# Homodyne_detector.net
KiCad netlist of a schematic drawn in Altium Designer
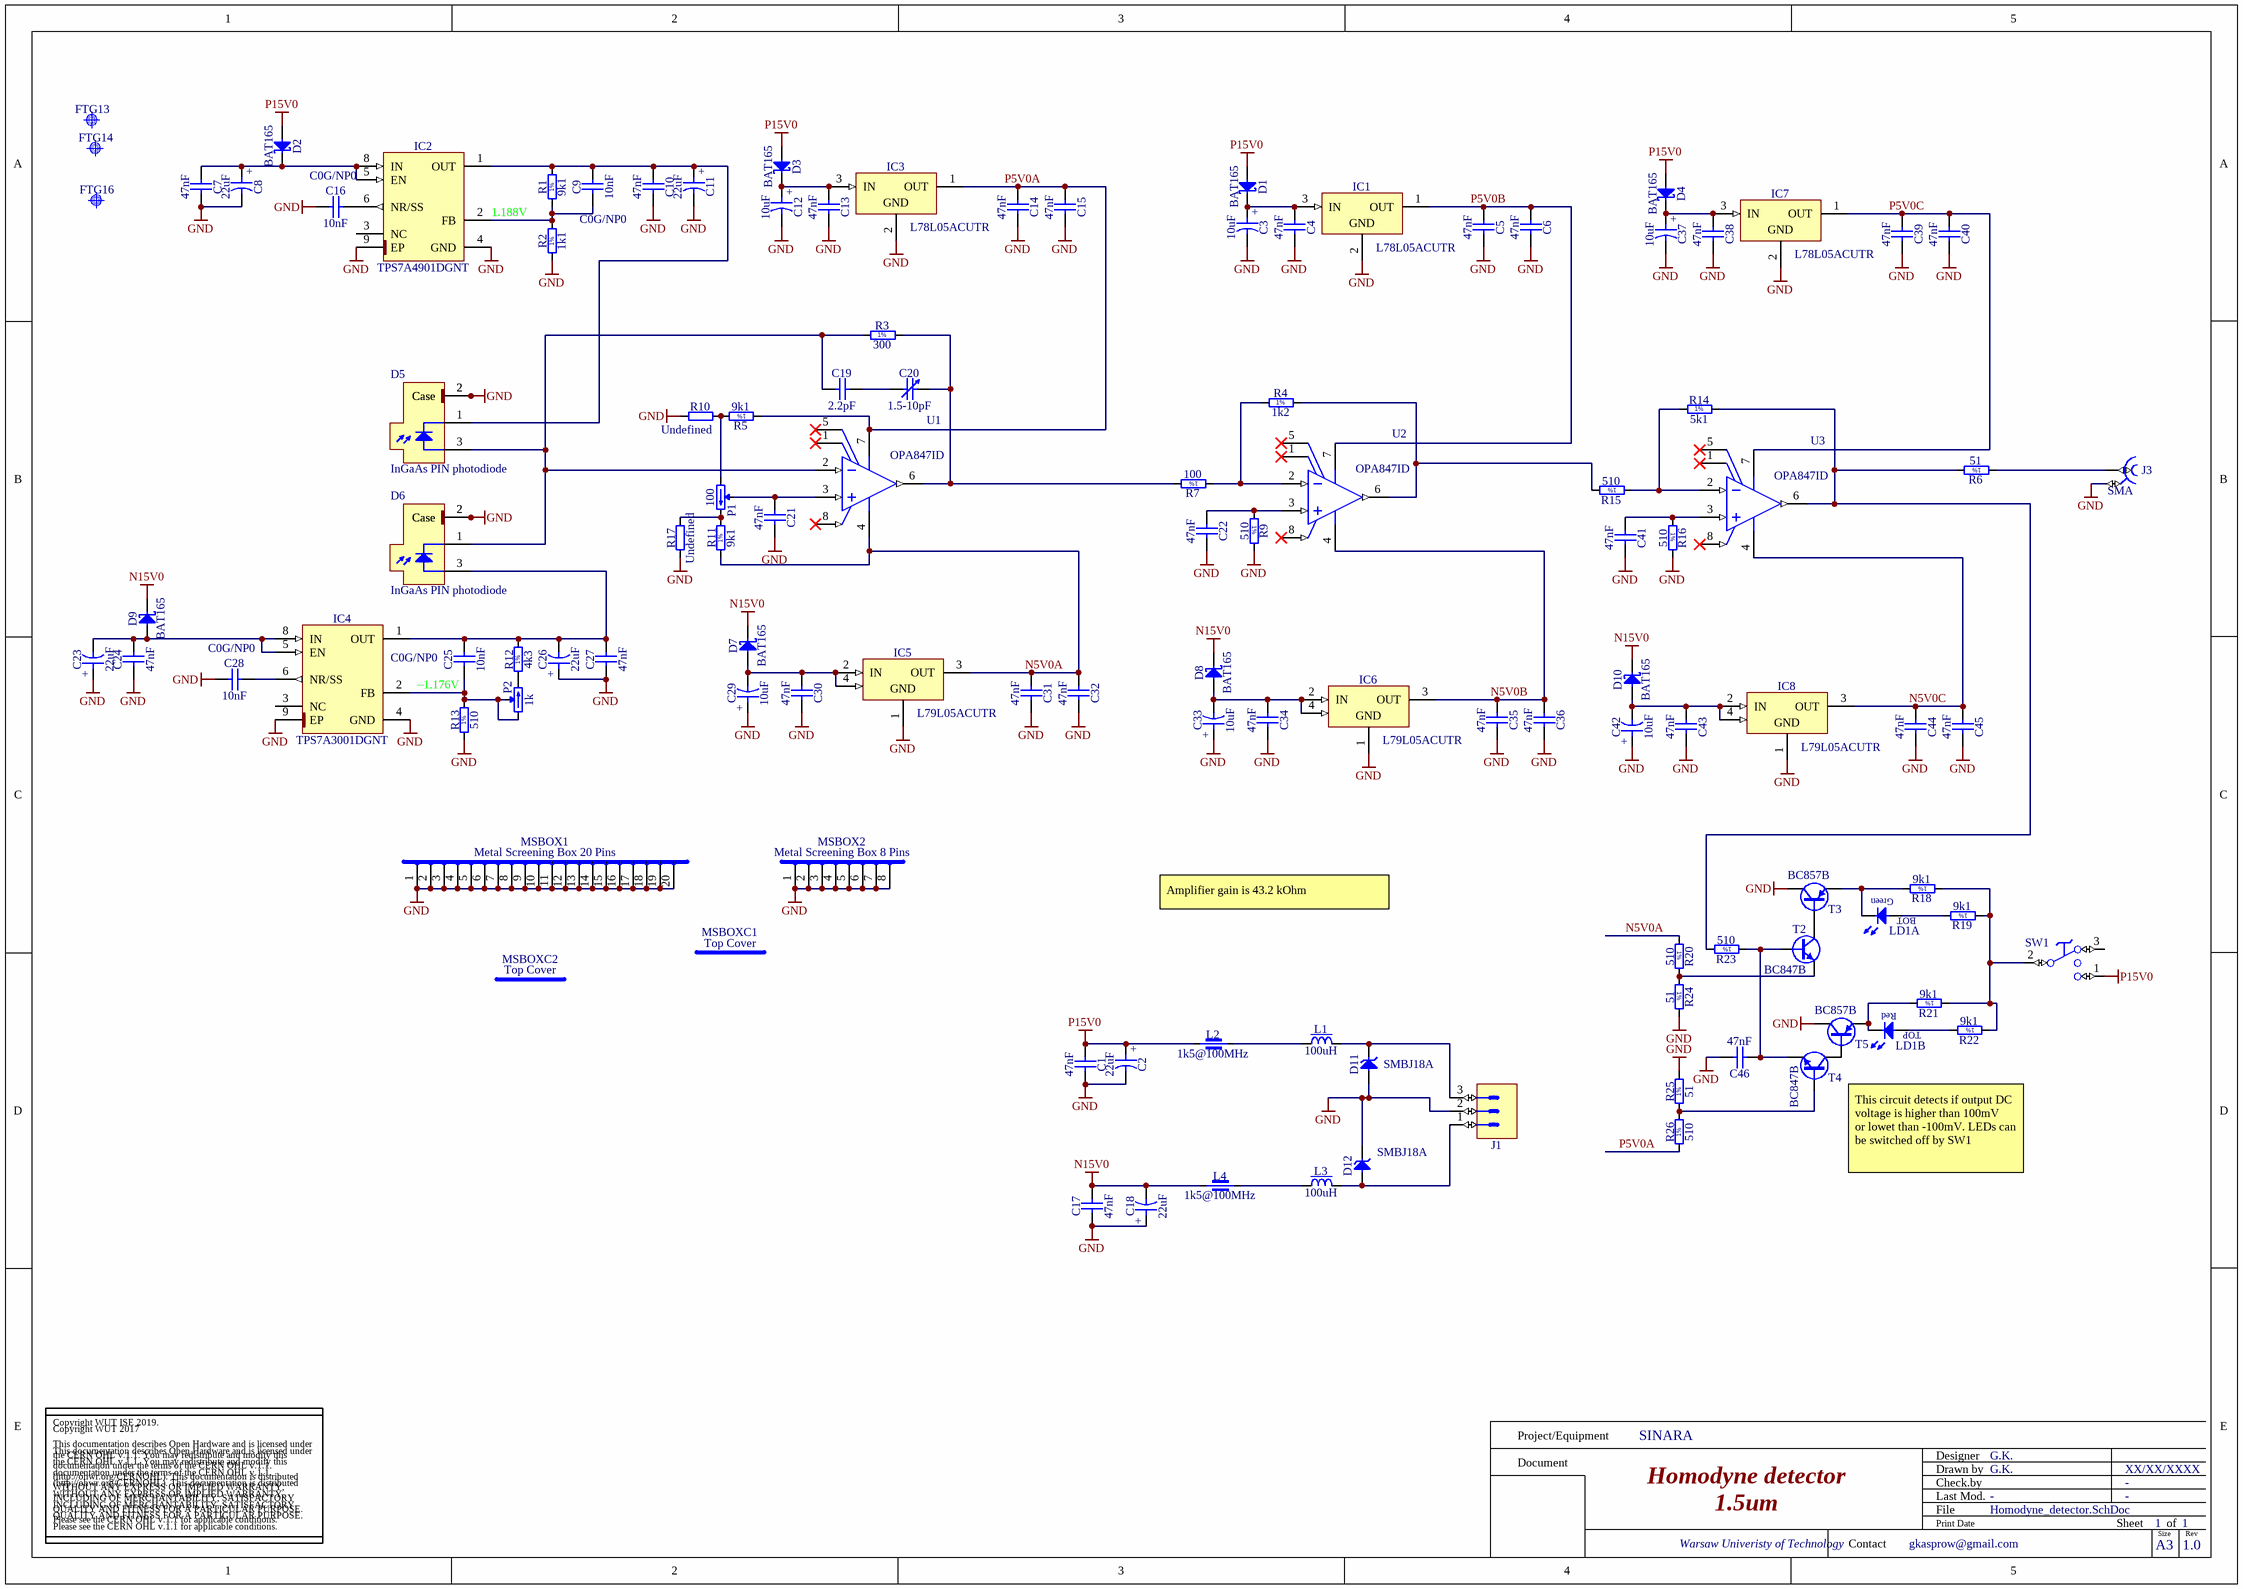
[diagram p0: Homodyne_detector.SchDoc]

(export (version "E")
  (design (tool "Eeschema 10.0.6"))
  (components
    (comp (ref "C1")
      (value "47nF")
      (footprint "CAPC2012X135N")
      (description "Non-polarised capacitor")
      (fields
        (field (name "PART NUMBER") "CC0805_47NF_25V_5%_C0G")
        (field (name "VOLTAGE") "25V")
        (field (name "AUTHOR") "CERN DEM JLC")
      )
      (libsource (lib "Capacitors") (part "Capacitor - non polarized"))
    )
    (comp (ref "C2")
      (value "22uF")
      (footprint "CAPMP7343X190N")
      (description "Polarised capacitor")
      (fields
        (field (name "PART NUMBER") "CTE7343-19_22UF_20V_20%_LESR0045_KEMET_T520")
        (field (name "VOLTAGE") "20V")
        (field (name "AUTHOR") "CERN DEM JLC")
      )
      (libsource (lib "Capacitors") (part "Capacitor - polarized"))
    )
    (comp (ref "C3")
      (value "10uF")
      (footprint "CAPAE430X540N")
      (description "Polarised capacitor")
      (fields
        (field (name "PART NUMBER") "CAE430-540_10UF_25V_20%")
        (field (name "VOLTAGE") "25V")
        (field (name "AUTHOR") "CERN DEM JLC")
      )
      (libsource (lib "Capacitors") (part "Capacitor - polarized"))
    )
    (comp (ref "C4")
      (value "47nF")
      (footprint "CAPC2012X135N")
      (description "Non-polarised capacitor")
      (fields
        (field (name "PART NUMBER") "CC0805_47NF_25V_5%_C0G")
        (field (name "VOLTAGE") "25V")
        (field (name "AUTHOR") "CERN DEM JLC")
      )
      (libsource (lib "Capacitors") (part "Capacitor - non polarized"))
    )
    (comp (ref "C5")
      (value "47nF")
      (footprint "CAPC2012X135N")
      (description "Non-polarised capacitor")
      (fields
        (field (name "PART NUMBER") "CC0805_47NF_25V_5%_C0G")
        (field (name "VOLTAGE") "25V")
        (field (name "AUTHOR") "CERN DEM JLC")
      )
      (libsource (lib "Capacitors") (part "Capacitor - non polarized"))
    )
    (comp (ref "C6")
      (value "47nF")
      (footprint "CAPC2012X135N")
      (description "Non-polarised capacitor")
      (fields
        (field (name "PART NUMBER") "CC0805_47NF_25V_5%_C0G")
        (field (name "VOLTAGE") "25V")
        (field (name "AUTHOR") "CERN DEM JLC")
      )
      (libsource (lib "Capacitors") (part "Capacitor - non polarized"))
    )
    (comp (ref "C7")
      (value "47nF")
      (footprint "CAPC2012X135N")
      (description "Non-polarised capacitor")
      (fields
        (field (name "PART NUMBER") "CC0805_47NF_25V_5%_C0G")
        (field (name "VOLTAGE") "25V")
        (field (name "AUTHOR") "CERN DEM JLC")
      )
      (libsource (lib "Capacitors") (part "Capacitor - non polarized"))
    )
    (comp (ref "C8")
      (value "22uF")
      (footprint "CAPMP7343X190N")
      (description "Polarised capacitor")
      (fields
        (field (name "PART NUMBER") "CTE7343-19_22UF_20V_20%_LESR0045_KEMET_T520")
        (field (name "VOLTAGE") "20V")
        (field (name "AUTHOR") "CERN DEM JLC")
      )
      (libsource (lib "Capacitors") (part "Capacitor - polarized"))
    )
    (comp (ref "C9")
      (value "10nF")
      (footprint "CAPC2012X135N")
      (description "Non-polarised capacitor")
      (fields
        (field (name "PART NUMBER") "CC0805_10NF_50V_5%_C0G")
        (field (name "VOLTAGE") "50V")
        (field (name "TC") "C0G/NP0")
        (field (name "AUTHOR") "CERN DEM JLC")
      )
      (libsource (lib "Capacitors") (part "Capacitor - non polarized"))
    )
    (comp (ref "C10")
      (value "47nF")
      (footprint "CAPC2012X135N")
      (description "Non-polarised capacitor")
      (fields
        (field (name "PART NUMBER") "CC0805_47NF_25V_5%_C0G")
        (field (name "VOLTAGE") "25V")
        (field (name "AUTHOR") "CERN DEM JLC")
      )
      (libsource (lib "Capacitors") (part "Capacitor - non polarized"))
    )
    (comp (ref "C11")
      (value "22uF")
      (footprint "CAPMP7343X190N")
      (description "Polarised capacitor")
      (fields
        (field (name "PART NUMBER") "CTE7343-19_22UF_20V_20%_LESR0045_KEMET_T520")
        (field (name "VOLTAGE") "20V")
        (field (name "AUTHOR") "CERN DEM JLC")
      )
      (libsource (lib "Capacitors") (part "Capacitor - polarized"))
    )
    (comp (ref "C12")
      (value "10uF")
      (footprint "CAPAE430X540N")
      (description "Polarised capacitor")
      (fields
        (field (name "PART NUMBER") "CAE430-540_10UF_25V_20%")
        (field (name "VOLTAGE") "25V")
        (field (name "AUTHOR") "CERN DEM JLC")
      )
      (libsource (lib "Capacitors") (part "Capacitor - polarized"))
    )
    (comp (ref "C13")
      (value "47nF")
      (footprint "CAPC2012X135N")
      (description "Non-polarised capacitor")
      (fields
        (field (name "PART NUMBER") "CC0805_47NF_25V_5%_C0G")
        (field (name "VOLTAGE") "25V")
        (field (name "AUTHOR") "CERN DEM JLC")
      )
      (libsource (lib "Capacitors") (part "Capacitor - non polarized"))
    )
    (comp (ref "C14")
      (value "47nF")
      (footprint "CAPC2012X135N")
      (description "Non-polarised capacitor")
      (fields
        (field (name "PART NUMBER") "CC0805_47NF_25V_5%_C0G")
        (field (name "VOLTAGE") "25V")
        (field (name "AUTHOR") "CERN DEM JLC")
      )
      (libsource (lib "Capacitors") (part "Capacitor - non polarized"))
    )
    (comp (ref "C15")
      (value "47nF")
      (footprint "CAPC2012X135N")
      (description "Non-polarised capacitor")
      (fields
        (field (name "PART NUMBER") "CC0805_47NF_25V_5%_C0G")
        (field (name "VOLTAGE") "25V")
        (field (name "AUTHOR") "CERN DEM JLC")
      )
      (libsource (lib "Capacitors") (part "Capacitor - non polarized"))
    )
    (comp (ref "C16")
      (value "10nF")
      (footprint "CAPC2012X135N")
      (description "Non-polarised capacitor")
      (fields
        (field (name "PART NUMBER") "CC0805_10NF_50V_5%_C0G")
        (field (name "VOLTAGE") "50V")
        (field (name "TC") "C0G/NP0")
        (field (name "AUTHOR") "CERN DEM JLC")
      )
      (libsource (lib "Capacitors") (part "Capacitor - non polarized"))
    )
    (comp (ref "C17")
      (value "47nF")
      (footprint "CAPC2012X135N")
      (description "Non-polarised capacitor")
      (fields
        (field (name "PART NUMBER") "CC0805_47NF_25V_5%_C0G")
        (field (name "VOLTAGE") "25V")
        (field (name "AUTHOR") "CERN DEM JLC")
      )
      (libsource (lib "Capacitors") (part "Capacitor - non polarized"))
    )
    (comp (ref "C18")
      (value "22uF")
      (footprint "CAPMP7343X190N")
      (description "Polarised capacitor")
      (fields
        (field (name "PART NUMBER") "CTE7343-19_22UF_20V_20%_LESR0045_KEMET_T520")
        (field (name "VOLTAGE") "20V")
        (field (name "AUTHOR") "CERN DEM JLC")
      )
      (libsource (lib "Capacitors") (part "Capacitor - polarized"))
    )
    (comp (ref "C19")
      (value "2.2pF")
      (footprint "CAPC1608X87N")
      (description "Non-polarised capacitor")
      (fields
        (field (name "PART NUMBER") "CC0603_2.2PF_50V_0.25PF_NP0")
        (field (name "VOLTAGE") "50V")
        (field (name "AUTHOR") "CERN DEM JLC")
      )
      (libsource (lib "Capacitors") (part "Capacitor - non polarized"))
    )
    (comp (ref "C20")
      (value "1.5-10pF")
      (footprint "CAPV_JOHANSON_9343")
      (description "Adjustable Capacitor")
      (fields
        (field (name "PART NUMBER") "CADJ_1.5-10PF_50V_JOHANSON_9343-14R1")
        (field (name "VOLTAGE") "50V")
        (field (name "AUTHOR") "CERN DEM JLC")
      )
      (libsource (lib "Capacitors") (part "Capacitor - Adjustable"))
    )
    (comp (ref "C21")
      (value "47nF")
      (footprint "CAPC2012X135N")
      (description "Non-polarised capacitor")
      (fields
        (field (name "PART NUMBER") "CC0805_47NF_25V_5%_C0G")
        (field (name "VOLTAGE") "25V")
        (field (name "AUTHOR") "CERN DEM JLC")
      )
      (libsource (lib "Capacitors") (part "Capacitor - non polarized"))
    )
    (comp (ref "C22")
      (value "47nF")
      (footprint "CAPC2012X135N")
      (description "Non-polarised capacitor")
      (fields
        (field (name "PART NUMBER") "CC0805_47NF_25V_5%_C0G")
        (field (name "VOLTAGE") "25V")
        (field (name "AUTHOR") "CERN DEM JLC")
      )
      (libsource (lib "Capacitors") (part "Capacitor - non polarized"))
    )
    (comp (ref "C23")
      (value "22uF")
      (footprint "CAPMP7343X190N")
      (description "Polarised capacitor")
      (fields
        (field (name "PART NUMBER") "CTE7343-19_22UF_20V_20%_LESR0045_KEMET_T520")
        (field (name "VOLTAGE") "20V")
        (field (name "AUTHOR") "CERN DEM JLC")
      )
      (libsource (lib "Capacitors") (part "Capacitor - polarized"))
    )
    (comp (ref "C24")
      (value "47nF")
      (footprint "CAPC2012X135N")
      (description "Non-polarised capacitor")
      (fields
        (field (name "PART NUMBER") "CC0805_47NF_25V_5%_C0G")
        (field (name "VOLTAGE") "25V")
        (field (name "AUTHOR") "CERN DEM JLC")
      )
      (libsource (lib "Capacitors") (part "Capacitor - non polarized"))
    )
    (comp (ref "C25")
      (value "10nF")
      (footprint "CAPC2012X135N")
      (description "Non-polarised capacitor")
      (fields
        (field (name "PART NUMBER") "CC0805_10NF_50V_5%_C0G")
        (field (name "VOLTAGE") "50V")
        (field (name "TC") "C0G/NP0")
        (field (name "AUTHOR") "CERN DEM JLC")
      )
      (libsource (lib "Capacitors") (part "Capacitor - non polarized"))
    )
    (comp (ref "C26")
      (value "22uF")
      (footprint "CAPMP7343X190N")
      (description "Polarised capacitor")
      (fields
        (field (name "PART NUMBER") "CTE7343-19_22UF_20V_20%_LESR0045_KEMET_T520")
        (field (name "VOLTAGE") "20V")
        (field (name "AUTHOR") "CERN DEM JLC")
      )
      (libsource (lib "Capacitors") (part "Capacitor - polarized"))
    )
    (comp (ref "C27")
      (value "47nF")
      (footprint "CAPC2012X135N")
      (description "Non-polarised capacitor")
      (fields
        (field (name "PART NUMBER") "CC0805_47NF_25V_5%_C0G")
        (field (name "VOLTAGE") "25V")
        (field (name "AUTHOR") "CERN DEM JLC")
      )
      (libsource (lib "Capacitors") (part "Capacitor - non polarized"))
    )
    (comp (ref "C28")
      (value "10nF")
      (footprint "CAPC2012X135N")
      (description "Non-polarised capacitor")
      (fields
        (field (name "PART NUMBER") "CC0805_10NF_50V_5%_C0G")
        (field (name "VOLTAGE") "50V")
        (field (name "TC") "C0G/NP0")
        (field (name "AUTHOR") "CERN DEM JLC")
      )
      (libsource (lib "Capacitors") (part "Capacitor - non polarized"))
    )
    (comp (ref "C29")
      (value "10uF")
      (footprint "CAPAE430X540N")
      (description "Polarised capacitor")
      (fields
        (field (name "PART NUMBER") "CAE430-540_10UF_25V_20%")
        (field (name "VOLTAGE") "25V")
        (field (name "AUTHOR") "CERN DEM JLC")
      )
      (libsource (lib "Capacitors") (part "Capacitor - polarized"))
    )
    (comp (ref "C30")
      (value "47nF")
      (footprint "CAPC2012X135N")
      (description "Non-polarised capacitor")
      (fields
        (field (name "PART NUMBER") "CC0805_47NF_25V_5%_C0G")
        (field (name "VOLTAGE") "25V")
        (field (name "AUTHOR") "CERN DEM JLC")
      )
      (libsource (lib "Capacitors") (part "Capacitor - non polarized"))
    )
    (comp (ref "C31")
      (value "47nF")
      (footprint "CAPC2012X135N")
      (description "Non-polarised capacitor")
      (fields
        (field (name "PART NUMBER") "CC0805_47NF_25V_5%_C0G")
        (field (name "VOLTAGE") "25V")
        (field (name "AUTHOR") "CERN DEM JLC")
      )
      (libsource (lib "Capacitors") (part "Capacitor - non polarized"))
    )
    (comp (ref "C32")
      (value "47nF")
      (footprint "CAPC2012X135N")
      (description "Non-polarised capacitor")
      (fields
        (field (name "PART NUMBER") "CC0805_47NF_25V_5%_C0G")
        (field (name "VOLTAGE") "25V")
        (field (name "AUTHOR") "CERN DEM JLC")
      )
      (libsource (lib "Capacitors") (part "Capacitor - non polarized"))
    )
    (comp (ref "C33")
      (value "10uF")
      (footprint "CAPAE430X540N")
      (description "Polarised capacitor")
      (fields
        (field (name "PART NUMBER") "CAE430-540_10UF_25V_20%")
        (field (name "VOLTAGE") "25V")
        (field (name "AUTHOR") "CERN DEM JLC")
      )
      (libsource (lib "Capacitors") (part "Capacitor - polarized"))
    )
    (comp (ref "C34")
      (value "47nF")
      (footprint "CAPC2012X135N")
      (description "Non-polarised capacitor")
      (fields
        (field (name "PART NUMBER") "CC0805_47NF_25V_5%_C0G")
        (field (name "VOLTAGE") "25V")
        (field (name "AUTHOR") "CERN DEM JLC")
      )
      (libsource (lib "Capacitors") (part "Capacitor - non polarized"))
    )
    (comp (ref "C35")
      (value "47nF")
      (footprint "CAPC2012X135N")
      (description "Non-polarised capacitor")
      (fields
        (field (name "PART NUMBER") "CC0805_47NF_25V_5%_C0G")
        (field (name "VOLTAGE") "25V")
        (field (name "AUTHOR") "CERN DEM JLC")
      )
      (libsource (lib "Capacitors") (part "Capacitor - non polarized"))
    )
    (comp (ref "C36")
      (value "47nF")
      (footprint "CAPC2012X135N")
      (description "Non-polarised capacitor")
      (fields
        (field (name "PART NUMBER") "CC0805_47NF_25V_5%_C0G")
        (field (name "VOLTAGE") "25V")
        (field (name "AUTHOR") "CERN DEM JLC")
      )
      (libsource (lib "Capacitors") (part "Capacitor - non polarized"))
    )
    (comp (ref "C37")
      (value "10uF")
      (footprint "CAPAE430X540N")
      (description "Polarised capacitor")
      (fields
        (field (name "PART NUMBER") "CAE430-540_10UF_25V_20%")
        (field (name "VOLTAGE") "25V")
        (field (name "AUTHOR") "CERN DEM JLC")
      )
      (libsource (lib "Capacitors") (part "Capacitor - polarized"))
    )
    (comp (ref "C38")
      (value "47nF")
      (footprint "CAPC2012X135N")
      (description "Non-polarised capacitor")
      (fields
        (field (name "PART NUMBER") "CC0805_47NF_25V_5%_C0G")
        (field (name "VOLTAGE") "25V")
        (field (name "AUTHOR") "CERN DEM JLC")
      )
      (libsource (lib "Capacitors") (part "Capacitor - non polarized"))
    )
    (comp (ref "C39")
      (value "47nF")
      (footprint "CAPC2012X135N")
      (description "Non-polarised capacitor")
      (fields
        (field (name "PART NUMBER") "CC0805_47NF_25V_5%_C0G")
        (field (name "VOLTAGE") "25V")
        (field (name "AUTHOR") "CERN DEM JLC")
      )
      (libsource (lib "Capacitors") (part "Capacitor - non polarized"))
    )
    (comp (ref "C40")
      (value "47nF")
      (footprint "CAPC2012X135N")
      (description "Non-polarised capacitor")
      (fields
        (field (name "PART NUMBER") "CC0805_47NF_25V_5%_C0G")
        (field (name "VOLTAGE") "25V")
        (field (name "AUTHOR") "CERN DEM JLC")
      )
      (libsource (lib "Capacitors") (part "Capacitor - non polarized"))
    )
    (comp (ref "C41")
      (value "47nF")
      (footprint "CAPC2012X135N")
      (description "Non-polarised capacitor")
      (fields
        (field (name "PART NUMBER") "CC0805_47NF_25V_5%_C0G")
        (field (name "VOLTAGE") "25V")
        (field (name "AUTHOR") "CERN DEM JLC")
      )
      (libsource (lib "Capacitors") (part "Capacitor - non polarized"))
    )
    (comp (ref "C42")
      (value "10uF")
      (footprint "CAPAE430X540N")
      (description "Polarised capacitor")
      (fields
        (field (name "PART NUMBER") "CAE430-540_10UF_25V_20%")
        (field (name "VOLTAGE") "25V")
        (field (name "AUTHOR") "CERN DEM JLC")
      )
      (libsource (lib "Capacitors") (part "Capacitor - polarized"))
    )
    (comp (ref "C43")
      (value "47nF")
      (footprint "CAPC2012X135N")
      (description "Non-polarised capacitor")
      (fields
        (field (name "PART NUMBER") "CC0805_47NF_25V_5%_C0G")
        (field (name "VOLTAGE") "25V")
        (field (name "AUTHOR") "CERN DEM JLC")
      )
      (libsource (lib "Capacitors") (part "Capacitor - non polarized"))
    )
    (comp (ref "C44")
      (value "47nF")
      (footprint "CAPC2012X135N")
      (description "Non-polarised capacitor")
      (fields
        (field (name "PART NUMBER") "CC0805_47NF_25V_5%_C0G")
        (field (name "VOLTAGE") "25V")
        (field (name "AUTHOR") "CERN DEM JLC")
      )
      (libsource (lib "Capacitors") (part "Capacitor - non polarized"))
    )
    (comp (ref "C45")
      (value "47nF")
      (footprint "CAPC2012X135N")
      (description "Non-polarised capacitor")
      (fields
        (field (name "PART NUMBER") "CC0805_47NF_25V_5%_C0G")
        (field (name "VOLTAGE") "25V")
        (field (name "AUTHOR") "CERN DEM JLC")
      )
      (libsource (lib "Capacitors") (part "Capacitor - non polarized"))
    )
    (comp (ref "C46")
      (value "47nF")
      (footprint "CAPC2012X135N")
      (description "Non-polarised capacitor")
      (fields
        (field (name "PART NUMBER") "CC0805_47NF_25V_5%_C0G")
        (field (name "VOLTAGE") "25V")
        (field (name "AUTHOR") "CERN DEM JLC")
      )
      (libsource (lib "Capacitors") (part "Capacitor - non polarized"))
    )
    (comp (ref "D1")
      (value "BAT165")
      (footprint "SOD2512X110N")
      (description "Schottky Diode")
      (fields
        (field (name "VOLTAGE") "40V")
        (field (name "POWER") "750mA")
        (field (name "AUTHOR") "CERN DEM JLC")
      )
      (libsource (lib "ICs And Semiconductors") (part "Diode Schottky"))
    )
    (comp (ref "D2")
      (value "BAT165")
      (footprint "SOD2512X110N")
      (description "Schottky Diode")
      (fields
        (field (name "VOLTAGE") "40V")
        (field (name "POWER") "750mA")
        (field (name "AUTHOR") "CERN DEM JLC")
      )
      (libsource (lib "ICs And Semiconductors") (part "Diode Schottky"))
    )
    (comp (ref "D3")
      (value "BAT165")
      (footprint "SOD2512X110N")
      (description "Schottky Diode")
      (fields
        (field (name "VOLTAGE") "40V")
        (field (name "POWER") "750mA")
        (field (name "AUTHOR") "CERN DEM JLC")
      )
      (libsource (lib "ICs And Semiconductors") (part "Diode Schottky"))
    )
    (comp (ref "D4")
      (value "BAT165")
      (footprint "SOD2512X110N")
      (description "Schottky Diode")
      (fields
        (field (name "VOLTAGE") "40V")
        (field (name "POWER") "750mA")
        (field (name "AUTHOR") "CERN DEM JLC")
      )
      (libsource (lib "ICs And Semiconductors") (part "Diode Schottky"))
    )
    (comp (ref "D5")
      (value "InGaAs PIN photodiode")
      (footprint "Hamamatsu_TO-18_H")
      (description "High Speed InGaAs Photodiode, Optical Communications, Single/Multi-Mode Fiber Optic Receiver")
      (fields
        (field (name "PART NUMBER") "G12180-003A")
        (field (name "MANUFACTURER") "Hamamatsu")
        (field (name "AUTHOR") "GK")
      )
      (libsource (lib "Diodes") (part "PhotoDiode_G12180-003A"))
    )
    (comp (ref "D6")
      (value "InGaAs PIN photodiode")
      (footprint "Hamamatsu_TO-18_H")
      (description "High Speed InGaAs Photodiode, Optical Communications, Single/Multi-Mode Fiber Optic Receiver")
      (fields
        (field (name "PART NUMBER") "G12180-003A")
        (field (name "MANUFACTURER") "Hamamatsu")
        (field (name "AUTHOR") "GK")
      )
      (libsource (lib "Diodes") (part "PhotoDiode_G12180-003A"))
    )
    (comp (ref "D7")
      (value "BAT165")
      (footprint "SOD2512X110N")
      (description "Schottky Diode")
      (fields
        (field (name "VOLTAGE") "40V")
        (field (name "POWER") "750mA")
        (field (name "AUTHOR") "CERN DEM JLC")
      )
      (libsource (lib "ICs And Semiconductors") (part "Diode Schottky"))
    )
    (comp (ref "D8")
      (value "BAT165")
      (footprint "SOD2512X110N")
      (description "Schottky Diode")
      (fields
        (field (name "VOLTAGE") "40V")
        (field (name "POWER") "750mA")
        (field (name "AUTHOR") "CERN DEM JLC")
      )
      (libsource (lib "ICs And Semiconductors") (part "Diode Schottky"))
    )
    (comp (ref "D9")
      (value "BAT165")
      (footprint "SOD2512X110N")
      (description "Schottky Diode")
      (fields
        (field (name "VOLTAGE") "40V")
        (field (name "POWER") "750mA")
        (field (name "AUTHOR") "CERN DEM JLC")
      )
      (libsource (lib "ICs And Semiconductors") (part "Diode Schottky"))
    )
    (comp (ref "D10")
      (value "BAT165")
      (footprint "SOD2512X110N")
      (description "Schottky Diode")
      (fields
        (field (name "VOLTAGE") "40V")
        (field (name "POWER") "750mA")
        (field (name "AUTHOR") "CERN DEM JLC")
      )
      (libsource (lib "ICs And Semiconductors") (part "Diode Schottky"))
    )
    (comp (ref "D11")
      (value "SMBJ18A")
      (footprint "DIOM5336X265N")
      (description "Zener Diode")
      (fields
        (field (name "VOLTAGE") "18V")
        (field (name "POWER") "600W")
        (field (name "AUTHOR") "CERN DEM JMW")
      )
      (libsource (lib "ICs And Semiconductors") (part "Diode Zener"))
    )
    (comp (ref "D12")
      (value "SMBJ18A")
      (footprint "DIOM5336X265N")
      (description "Zener Diode")
      (fields
        (field (name "VOLTAGE") "18V")
        (field (name "POWER") "600W")
        (field (name "AUTHOR") "CERN DEM JMW")
      )
      (libsource (lib "ICs And Semiconductors") (part "Diode Zener"))
    )
    (comp (ref "FTG13")
      (value "Use only in PCB")
      (footprint "FIDUCIAL_TOP_C100-200")
      (description "Fiducial Target")
      (fields (field (name "PART NUMBER") "FIDUCIAL_TARGET_C100-200") (field (name "AUTHOR") "CERN DEM JLC"))
      (libsource (lib "Eletro-mechanical") (part "Fiducial Target"))
    )
    (comp (ref "FTG14")
      (value "Use only in PCB")
      (footprint "FIDUCIAL_TOP_S100-200")
      (description "Fiducial Target")
      (fields (field (name "PART NUMBER") "FIDUCIAL_TARGET_S100-200") (field (name "AUTHOR") "CERN DEM JLC"))
      (libsource (lib "Eletro-mechanical") (part "Fiducial Target"))
    )
    (comp (ref "FTG16")
      (value "Use only in PCB")
      (footprint "FIDUCIAL_TOP_S100-200")
      (description "Fiducial Target")
      (fields (field (name "PART NUMBER") "FIDUCIAL_TARGET_S100-200") (field (name "AUTHOR") "CERN DEM JLC"))
      (libsource (lib "Eletro-mechanical") (part "Fiducial Target"))
    )
    (comp (ref "IC1")
      (value "L78L05ACUTR")
      (footprint "SOT89")
      (description "3-Terminal Regulator 1=OUT 2=GND 3=IN")
      (fields (field (name "MANUFACTURER") "ST MICROELECTRONICS") (field (name "AUTHOR") "CERN DEM JLC"))
      (libsource (lib "ICs And Semiconductors") (part "REG3 1OUT-2GND-3IN"))
    )
    (comp (ref "IC2")
      (value "TPS7A4901DGNT")
      (footprint "SOP65P490X110-9N-R157X189")
      (description "+36V, +150mA, Ultralow-Noise, Positive Linear Regulator")
      (fields (field (name "MANUFACTURER") "TEXAS INSTRUMENTS") (field (name "AUTHOR") "CERN DEM JLC"))
      (libsource (lib "ICs And Semiconductors") (part "TPS7A4901DGN"))
    )
    (comp (ref "IC3")
      (value "L78L05ACUTR")
      (footprint "SOT89")
      (description "3-Terminal Regulator 1=OUT 2=GND 3=IN")
      (fields (field (name "MANUFACTURER") "ST MICROELECTRONICS") (field (name "AUTHOR") "CERN DEM JLC"))
      (libsource (lib "ICs And Semiconductors") (part "REG3 1OUT-2GND-3IN"))
    )
    (comp (ref "IC4")
      (value "TPS7A3001DGNT")
      (footprint "SOP65P490X110-9N-R157X189")
      (description "-36V, -200mA, Ultralow-Noise, Negative Linear Regulator")
      (fields (field (name "MANUFACTURER") "TEXAS INSTRUMENTS") (field (name "AUTHOR") "CERN DEM JLC"))
      (libsource (lib "ICs And Semiconductors") (part "TPS7A3001DGN"))
    )
    (comp (ref "IC5")
      (value "L79L05ACUTR")
      (footprint "SOT89")
      (description "3-Terminal Regulator 1=GND 2=IN 3=OUT 4=IN")
      (fields (field (name "MANUFACTURER") "ST MICROELECTRONICS") (field (name "AUTHOR") "CERN DEM JLC"))
      (libsource (lib "ICs And Semiconductors") (part "REG3+1 1GND-2IN-3OUT+4IN"))
    )
    (comp (ref "IC6")
      (value "L79L05ACUTR")
      (footprint "SOT89")
      (description "3-Terminal Regulator 1=GND 2=IN 3=OUT 4=IN")
      (fields (field (name "MANUFACTURER") "ST MICROELECTRONICS") (field (name "AUTHOR") "CERN DEM JLC"))
      (libsource (lib "ICs And Semiconductors") (part "REG3+1 1GND-2IN-3OUT+4IN"))
    )
    (comp (ref "IC7")
      (value "L78L05ACUTR")
      (footprint "SOT89")
      (description "3-Terminal Regulator 1=OUT 2=GND 3=IN")
      (fields (field (name "MANUFACTURER") "ST MICROELECTRONICS") (field (name "AUTHOR") "CERN DEM JLC"))
      (libsource (lib "ICs And Semiconductors") (part "REG3 1OUT-2GND-3IN"))
    )
    (comp (ref "IC8")
      (value "L79L05ACUTR")
      (footprint "SOT89")
      (description "3-Terminal Regulator 1=GND 2=IN 3=OUT 4=IN")
      (fields (field (name "MANUFACTURER") "ST MICROELECTRONICS") (field (name "AUTHOR") "CERN DEM JLC"))
      (libsource (lib "ICs And Semiconductors") (part "REG3+1 1GND-2IN-3OUT+4IN"))
    )
    (comp (ref "J1")
      (value "~")
      (footprint "PHOENIX_1757255")
      (description "Connector 3 Male")
      (fields
        (field (name "PART NUMBER") "PHOENIX_1757255")
        (field (name "MANUFACTURER") "PHOENIX CONTACT")
        (field (name "AUTHOR") "CERN DEM JLC")
      )
      (libsource (lib "Connectors") (part "Connector 3 Male"))
    )
    (comp (ref "J3")
      (value "SMA")
      (footprint "RF249BT0050GHDW")
      (description "50 Ohm Through Hole SMA Right Angle PCB Jack")
      (fields
        (field (name "PART NUMBER") "AdamTech_RF249BT0050GHDW")
        (field (name "MANUFACTURER") "AdamTech")
        (field (name "AUTHOR") "GK")
      )
      (libsource (lib "Connectors") (part "CON_SMA_RF249BT0050GHDW"))
    )
    (comp (ref "L1")
      (value "100uH")
      (footprint "INDM5650X530N")
      (description "Inductor With Core")
      (fields
        (field (name "PART NUMBER") "IND2220_100UH_10%_EPCOS_B82442H")
        (field (name "POWER") "350mA")
        (field (name "AUTHOR") "CERN DEM JLC")
      )
      (libsource (lib "Inductors & Transformers") (part "Inductor With Magnetic core"))
    )
    (comp (ref "L2")
      (value "1k5@100MHz")
      (footprint "INDC2012X110N")
      (fields
        (field (name "PART NUMBER") "IND0805_WURTH_742792097")
        (field (name "POWER") "1A")
        (field (name "TOLERANCE") "±25%")
        (field (name "AUTHOR") "CERN DEM MR")
      )
      (libsource (lib "Inductors & Transformers") (part "Ferrite Bead"))
    )
    (comp (ref "L3")
      (value "100uH")
      (footprint "INDM5650X530N")
      (description "Inductor With Core")
      (fields
        (field (name "PART NUMBER") "IND2220_100UH_10%_EPCOS_B82442H")
        (field (name "POWER") "350mA")
        (field (name "AUTHOR") "CERN DEM JLC")
      )
      (libsource (lib "Inductors & Transformers") (part "Inductor With Magnetic core"))
    )
    (comp (ref "L4")
      (value "1k5@100MHz")
      (footprint "INDC2012X110N")
      (fields
        (field (name "PART NUMBER") "IND0805_WURTH_742792097")
        (field (name "POWER") "1A")
        (field (name "TOLERANCE") "±25%")
        (field (name "AUTHOR") "CERN DEM MR")
      )
      (libsource (lib "Inductors & Transformers") (part "Ferrite Bead"))
    )
    (comp (ref "LD1")
      (value "Red/Green")
      (footprint "LED_DIALIGHT_571-0112F")
      (description "2x LED  Botom Green, Top Red")
      (fields
        (field (name "PART NUMBER") "LED_DIALIGHT_571-0112F")
        (field (name "MANUFACTURER") "DIALIGHT")
        (field (name "AUTHOR") "CERN DEM JLC")
      )
      (libsource (lib "ICs And Semiconductors") (part "LED x2 G-1C2A-BOT_R-3C4A-TOP"))
    )
    (comp (ref "MSBOX1")
      (value "Metal Screening Box 20 Pins")
      (footprint "MSBOX_LAIRD_BMI-S-205-F")
      (fields
        (field (name "PART NUMBER") "MSBOX_LAIRD_BMI-S-205-F")
        (field (name "MANUFACTURER") "LAIRD")
        (field (name "MANUFACTURER PART NUMBER") "BMI-S-205-F")
        (field (name "AUTHOR") "CERN DEM JLC")
      )
      (libsource (lib "Eletro-mechanical") (part "Metal Screening Box - 20 pins"))
    )
    (comp (ref "MSBOX2")
      (value "Metal Screening Box 8 Pins")
      (footprint "MSBOX_LAIRD_BMI-S-202-F")
      (fields
        (field (name "PART NUMBER") "MSBOX_LAIRD_BMI-S-202-F")
        (field (name "MANUFACTURER") "LAIRD")
        (field (name "MANUFACTURER PART NUMBER") "BMI-S-202-F")
        (field (name "AUTHOR") "CERN DEM JLC")
      )
      (libsource (lib "Eletro-mechanical") (part "Metal Screening Box - 8 pins"))
    )
    (comp (ref "MSBOXC1")
      (value "Top Cover")
      (footprint "MSBOX_LAIRD_BMI-S-202-C")
      (description "Metal Screening Box - Top Cover 0 Pin")
      (fields
        (field (name "PART NUMBER") "MSBOX_LAIRD_BMI-S-202-C")
        (field (name "MANUFACTURER") "LAIRD")
        (field (name "AUTHOR") "CERN DEM JLC")
      )
      (libsource (lib "Eletro-mechanical") (part "Metal Screening Box - Top Cover"))
    )
    (comp (ref "MSBOXC2")
      (value "Top Cover")
      (footprint "MSBOX_LAIRD_BMI-S-205-C")
      (description "Metal Screening Box - Top Cover 0 Pin")
      (fields
        (field (name "PART NUMBER") "MSBOX_LAIRD_BMI-S-205-C")
        (field (name "MANUFACTURER") "LAIRD")
        (field (name "AUTHOR") "CERN DEM JLC")
      )
      (libsource (lib "Eletro-mechanical") (part "Metal Screening Box - Top Cover"))
    )
    (comp (ref "P1")
      (value "100")
      (footprint "TRIM_BOURNS_3006P")
      (description "Trimming Potentiometer")
      (fields
        (field (name "PART NUMBER") "TRIM_15T_100R_BOURNS_3006P-1-101LF")
        (field (name "POWER") "0.75W")
        (field (name "AUTHOR") "CERN DEM JLC")
      )
      (libsource (lib "Resistors") (part "Trimming Potentiometer"))
    )
    (comp (ref "P2")
      (value "1k")
      (footprint "TRIM_BOURNS_3314G-1")
      (description "Trimming Potentiometer")
      (fields
        (field (name "PART NUMBER") "TRIM_1T_1K_BOURNS_3314G-1-102E")
        (field (name "POWER") "0.25W")
        (field (name "AUTHOR") "CERN DEM JLC")
      )
      (libsource (lib "Resistors") (part "Trimming Potentiometer"))
    )
    (comp (ref "R1")
      (value "9k1")
      (footprint "RESC1608X55N")
      (description "Resistor - 1%")
      (fields
        (field (name "PART NUMBER") "R0603_9K1_1%_0.1W_100PPM")
        (field (name "POWER") "0.1W")
        (field (name "AUTHOR") "CERN DEM JLC")
      )
      (libsource (lib "Resistors") (part "Resistor - 1%"))
    )
    (comp (ref "R2")
      (value "1k1")
      (footprint "RESC1608X55N")
      (description "Resistor - 1%")
      (fields
        (field (name "PART NUMBER") "R0603_1K1_1%_0.1W_100PPM")
        (field (name "POWER") "0.1W")
        (field (name "AUTHOR") "CERN DEM JLC")
      )
      (libsource (lib "Resistors") (part "Resistor - 1%"))
    )
    (comp (ref "R3")
      (value "300")
      (footprint "RESC1608X55N")
      (description "Resistor - 1%")
      (fields
        (field (name "PART NUMBER") "R0603_300R_1%_0.1W_100PPM")
        (field (name "POWER") "0.1W")
        (field (name "AUTHOR") "CERN DEM JLC")
      )
      (libsource (lib "Resistors") (part "Resistor - 1%"))
    )
    (comp (ref "R4")
      (value "1k2")
      (footprint "RESC1608X55N")
      (description "Resistor - 1%")
      (fields
        (field (name "PART NUMBER") "R0603_1K2_1%_0.1W_100PPM")
        (field (name "POWER") "0.1W")
        (field (name "AUTHOR") "CERN DEM JLC")
      )
      (libsource (lib "Resistors") (part "Resistor - 1%"))
    )
    (comp (ref "R5")
      (value "9k1")
      (footprint "RESC1608X55N")
      (description "Resistor - 1%")
      (fields
        (field (name "PART NUMBER") "R0603_9K1_1%_0.1W_100PPM")
        (field (name "POWER") "0.1W")
        (field (name "AUTHOR") "CERN DEM JLC")
      )
      (libsource (lib "Resistors") (part "Resistor - 1%"))
    )
    (comp (ref "R6")
      (value "51")
      (footprint "RESC1608X55N")
      (description "Resistor - 1%")
      (fields
        (field (name "PART NUMBER") "R0603_51R_1%_0.1W_100PPM")
        (field (name "POWER") "0.1W")
        (field (name "AUTHOR") "CERN DEM JLC")
      )
      (libsource (lib "Resistors") (part "Resistor - 1%"))
    )
    (comp (ref "R7")
      (value "100")
      (footprint "RESC1608X55N")
      (description "Resistor - 1%")
      (fields
        (field (name "PART NUMBER") "R0603_100R_1%_0.1W_100PPM")
        (field (name "POWER") "0.1W")
        (field (name "AUTHOR") "CERN DEM JLC")
      )
      (libsource (lib "Resistors") (part "Resistor - 1%"))
    )
    (comp (ref "R9")
      (value "510")
      (footprint "RESC1608X55N")
      (description "Resistor - 1%")
      (fields
        (field (name "PART NUMBER") "R0603_510R_1%_0.1W_100PPM")
        (field (name "POWER") "0.1W")
        (field (name "AUTHOR") "CERN DEM JLC")
      )
      (libsource (lib "Resistors") (part "Resistor - 1%"))
    )
    (comp (ref "R10")
      (value "Undefined")
      (footprint "RESC1608X55N")
      (description "Resistor")
      (fields (field (name "PART NUMBER") "R0603_NO-VALUE") (field (name "AUTHOR") "CERN DEM JLC"))
      (libsource (lib "Resistors") (part "Resistor"))
    )
    (comp (ref "R11")
      (value "9k1")
      (footprint "RESC1608X55N")
      (description "Resistor - 1%")
      (fields
        (field (name "PART NUMBER") "R0603_9K1_1%_0.1W_100PPM")
        (field (name "POWER") "0.1W")
        (field (name "AUTHOR") "CERN DEM JLC")
      )
      (libsource (lib "Resistors") (part "Resistor - 1%"))
    )
    (comp (ref "R12")
      (value "4k3")
      (footprint "RESC1608X55N")
      (description "Resistor - 1%")
      (fields
        (field (name "PART NUMBER") "R0603_4K3_1%_0.1W_100PPM")
        (field (name "POWER") "0.1W")
        (field (name "AUTHOR") "CERN DEM JLC")
      )
      (libsource (lib "Resistors") (part "Resistor - 1%"))
    )
    (comp (ref "R13")
      (value "510")
      (footprint "RESC1608X55N")
      (description "Resistor - 1%")
      (fields
        (field (name "PART NUMBER") "R0603_510R_1%_0.1W_100PPM")
        (field (name "POWER") "0.1W")
        (field (name "AUTHOR") "CERN DEM JLC")
      )
      (libsource (lib "Resistors") (part "Resistor - 1%"))
    )
    (comp (ref "R14")
      (value "5k1")
      (footprint "RESC1608X55N")
      (description "Resistor - 1%")
      (fields
        (field (name "PART NUMBER") "R0603_5K1_1%_0.1W_100PPM")
        (field (name "POWER") "0.1W")
        (field (name "AUTHOR") "CERN DEM JLC")
      )
      (libsource (lib "Resistors") (part "Resistor - 1%"))
    )
    (comp (ref "R15")
      (value "510")
      (footprint "RESC1608X55N")
      (description "Resistor - 1%")
      (fields
        (field (name "PART NUMBER") "R0603_510R_1%_0.1W_100PPM")
        (field (name "POWER") "0.1W")
        (field (name "AUTHOR") "CERN DEM JLC")
      )
      (libsource (lib "Resistors") (part "Resistor - 1%"))
    )
    (comp (ref "R16")
      (value "510")
      (footprint "RESC1608X55N")
      (description "Resistor - 1%")
      (fields
        (field (name "PART NUMBER") "R0603_510R_1%_0.1W_100PPM")
        (field (name "POWER") "0.1W")
        (field (name "AUTHOR") "CERN DEM JLC")
      )
      (libsource (lib "Resistors") (part "Resistor - 1%"))
    )
    (comp (ref "R17")
      (value "Undefined")
      (footprint "RESC1608X55N")
      (description "Resistor")
      (fields (field (name "PART NUMBER") "R0603_NO-VALUE") (field (name "AUTHOR") "CERN DEM JLC"))
      (libsource (lib "Resistors") (part "Resistor"))
    )
    (comp (ref "R18")
      (value "9k1")
      (footprint "RESC1608X55N")
      (description "Resistor - 1%")
      (fields
        (field (name "PART NUMBER") "R0603_9K1_1%_0.1W_100PPM")
        (field (name "POWER") "0.1W")
        (field (name "AUTHOR") "CERN DEM JLC")
      )
      (libsource (lib "Resistors") (part "Resistor - 1%"))
    )
    (comp (ref "R19")
      (value "9k1")
      (footprint "RESC1608X55N")
      (description "Resistor - 1%")
      (fields
        (field (name "PART NUMBER") "R0603_9K1_1%_0.1W_100PPM")
        (field (name "POWER") "0.1W")
        (field (name "AUTHOR") "CERN DEM JLC")
      )
      (libsource (lib "Resistors") (part "Resistor - 1%"))
    )
    (comp (ref "R20")
      (value "510")
      (footprint "RESC1608X55N")
      (description "Resistor - 1%")
      (fields
        (field (name "PART NUMBER") "R0603_510R_1%_0.1W_100PPM")
        (field (name "POWER") "0.1W")
        (field (name "AUTHOR") "CERN DEM JLC")
      )
      (libsource (lib "Resistors") (part "Resistor - 1%"))
    )
    (comp (ref "R21")
      (value "9k1")
      (footprint "RESC1608X55N")
      (description "Resistor - 1%")
      (fields
        (field (name "PART NUMBER") "R0603_9K1_1%_0.1W_100PPM")
        (field (name "POWER") "0.1W")
        (field (name "AUTHOR") "CERN DEM JLC")
      )
      (libsource (lib "Resistors") (part "Resistor - 1%"))
    )
    (comp (ref "R22")
      (value "9k1")
      (footprint "RESC1608X55N")
      (description "Resistor - 1%")
      (fields
        (field (name "PART NUMBER") "R0603_9K1_1%_0.1W_100PPM")
        (field (name "POWER") "0.1W")
        (field (name "AUTHOR") "CERN DEM JLC")
      )
      (libsource (lib "Resistors") (part "Resistor - 1%"))
    )
    (comp (ref "R23")
      (value "510")
      (footprint "RESC1608X55N")
      (description "Resistor - 1%")
      (fields
        (field (name "PART NUMBER") "R0603_510R_1%_0.1W_100PPM")
        (field (name "POWER") "0.1W")
        (field (name "AUTHOR") "CERN DEM JLC")
      )
      (libsource (lib "Resistors") (part "Resistor - 1%"))
    )
    (comp (ref "R24")
      (value "51")
      (footprint "RESC1608X55N")
      (description "Resistor - 1%")
      (fields
        (field (name "PART NUMBER") "R0603_51R_1%_0.1W_100PPM")
        (field (name "POWER") "0.1W")
        (field (name "AUTHOR") "CERN DEM JLC")
      )
      (libsource (lib "Resistors") (part "Resistor - 1%"))
    )
    (comp (ref "R25")
      (value "51")
      (footprint "RESC1608X55N")
      (description "Resistor - 1%")
      (fields
        (field (name "PART NUMBER") "R0603_51R_1%_0.1W_100PPM")
        (field (name "POWER") "0.1W")
        (field (name "AUTHOR") "CERN DEM JLC")
      )
      (libsource (lib "Resistors") (part "Resistor - 1%"))
    )
    (comp (ref "R26")
      (value "510")
      (footprint "RESC1608X55N")
      (description "Resistor - 1%")
      (fields
        (field (name "PART NUMBER") "R0603_510R_1%_0.1W_100PPM")
        (field (name "POWER") "0.1W")
        (field (name "AUTHOR") "CERN DEM JLC")
      )
      (libsource (lib "Resistors") (part "Resistor - 1%"))
    )
    (comp (ref "SW1")
      (value "Switch")
      (footprint "SW_NKK_A13AV")
      (description "SPDT Switch")
      (fields
        (field (name "PART NUMBER") "SW_NKK_A13AV")
        (field (name "MANUFACTURER") "NKK SWITCHES")
        (field (name "AUTHOR") "CERN DEM MR")
      )
      (libsource (lib "Eletro-mechanical") (part "SW SPDT 1NO-2C-3NC (ON-OFF-ON)"))
    )
    (comp (ref "T2")
      (value "BC847B")
      (footprint "SOT95P230X110-3N")
      (description "NPN Transistor")
      (fields (field (name "MANUFACTURER") "NXP SEMICONDUCTORS") (field (name "AUTHOR") "CERN DEM JLC"))
      (libsource (lib "ICs And Semiconductors") (part "NPN B1 E2 C3"))
    )
    (comp (ref "T3")
      (value "BC857B")
      (footprint "SOT95P230X110-3N")
      (description "PNP Transistor")
      (fields (field (name "MANUFACTURER") "NXP SEMICONDUCTORS") (field (name "AUTHOR") "CERN DEM JLC"))
      (libsource (lib "ICs And Semiconductors") (part "PNP B1 E2 C3"))
    )
    (comp (ref "T4")
      (value "BC847B")
      (footprint "SOT95P230X110-3N")
      (description "NPN Transistor")
      (fields (field (name "MANUFACTURER") "NXP SEMICONDUCTORS") (field (name "AUTHOR") "CERN DEM JLC"))
      (libsource (lib "ICs And Semiconductors") (part "NPN B1 E2 C3"))
    )
    (comp (ref "T5")
      (value "BC857B")
      (footprint "SOT95P230X110-3N")
      (description "PNP Transistor")
      (fields (field (name "MANUFACTURER") "NXP SEMICONDUCTORS") (field (name "AUTHOR") "CERN DEM JLC"))
      (libsource (lib "ICs And Semiconductors") (part "PNP B1 E2 C3"))
    )
    (comp (ref "U1")
      (value "OPA847ID")
      (footprint "D0008A_L")
      (fields (field (name "MANUFACTURER") "Texas Instruments"))
      (libsource (lib "Altium Content Vault") (part "TI-OPA847D8"))
    )
    (comp (ref "U2")
      (value "OPA847ID")
      (footprint "D0008A_L")
      (fields (field (name "MANUFACTURER") "Texas Instruments"))
      (libsource (lib "Altium Content Vault") (part "TI-OPA847D8"))
    )
    (comp (ref "U3")
      (value "OPA847ID")
      (footprint "D0008A_L")
      (fields (field (name "MANUFACTURER") "Texas Instruments"))
      (libsource (lib "Altium Content Vault") (part "TI-OPA847D8"))
    )
  )
  (nets
    (net (code "1") (name "/N5V0A") (class "Default")
      (node (ref "C31") (pin "1") (pinfunction "1_1") (pintype "passive"))
      (node (ref "C32") (pin "1") (pinfunction "1_1") (pintype "passive"))
      (node (ref "IC5") (pin "3") (pinfunction "OUT_3") (pintype "power_in"))
      (node (ref "R11") (pin "1") (pinfunction "1_1") (pintype "passive"))
      (node (ref "R20") (pin "1") (pinfunction "1_1") (pintype "passive"))
      (node (ref "U1") (pin "4") (pinfunction "VS-_4") (pintype "power_in"))
    )
    (net (code "2") (name "/N5V0B") (class "Default")
      (node (ref "C35") (pin "1") (pinfunction "1_1") (pintype "passive"))
      (node (ref "C36") (pin "1") (pinfunction "1_1") (pintype "passive"))
      (node (ref "IC6") (pin "3") (pinfunction "OUT_3") (pintype "power_in"))
      (node (ref "U2") (pin "4") (pinfunction "VS-_4") (pintype "power_in"))
    )
    (net (code "3") (name "/N5V0C") (class "Default")
      (node (ref "C44") (pin "1") (pinfunction "1_1") (pintype "passive"))
      (node (ref "C45") (pin "1") (pinfunction "1_1") (pintype "passive"))
      (node (ref "IC8") (pin "3") (pinfunction "OUT_3") (pintype "power_in"))
      (node (ref "U3") (pin "4") (pinfunction "VS-_4") (pintype "power_in"))
    )
    (net (code "4") (name "/P5V0A") (class "Default")
      (node (ref "C14") (pin "1") (pinfunction "1_1") (pintype "passive"))
      (node (ref "C15") (pin "1") (pinfunction "1_1") (pintype "passive"))
      (node (ref "IC3") (pin "1") (pinfunction "OUT_1") (pintype "power_in"))
      (node (ref "R26") (pin "1") (pinfunction "1_1") (pintype "passive"))
      (node (ref "R5") (pin "1") (pinfunction "1_1") (pintype "passive"))
      (node (ref "U1") (pin "7") (pinfunction "VS+_7") (pintype "power_in"))
    )
    (net (code "5") (name "/P5V0B") (class "Default")
      (node (ref "C5") (pin "1") (pinfunction "1_1") (pintype "passive"))
      (node (ref "C6") (pin "1") (pinfunction "1_1") (pintype "passive"))
      (node (ref "IC1") (pin "1") (pinfunction "OUT_1") (pintype "power_in"))
      (node (ref "U2") (pin "7") (pinfunction "VS+_7") (pintype "power_in"))
    )
    (net (code "6") (name "/P5V0C") (class "Default")
      (node (ref "C39") (pin "1") (pinfunction "1_1") (pintype "passive"))
      (node (ref "C40") (pin "1") (pinfunction "1_1") (pintype "passive"))
      (node (ref "IC7") (pin "1") (pinfunction "OUT_1") (pintype "power_in"))
      (node (ref "U3") (pin "7") (pinfunction "VS+_7") (pintype "power_in"))
    )
    (net (code "7") (name "GND") (class "Default")
      (node (ref "C1") (pin "2") (pinfunction "2_2") (pintype "passive"))
      (node (ref "C10") (pin "2") (pinfunction "2_2") (pintype "passive"))
      (node (ref "C11") (pin "2") (pinfunction "2_2") (pintype "passive"))
      (node (ref "C12") (pin "2") (pinfunction "2_2") (pintype "passive"))
      (node (ref "C13") (pin "2") (pinfunction "2_2") (pintype "passive"))
      (node (ref "C14") (pin "2") (pinfunction "2_2") (pintype "passive"))
      (node (ref "C15") (pin "2") (pinfunction "2_2") (pintype "passive"))
      (node (ref "C16") (pin "1") (pinfunction "1_1") (pintype "passive"))
      (node (ref "C17") (pin "1") (pinfunction "1_1") (pintype "passive"))
      (node (ref "C18") (pin "1") (pinfunction "1_1") (pintype "passive"))
      (node (ref "C2") (pin "2") (pinfunction "2_2") (pintype "passive"))
      (node (ref "C21") (pin "2") (pinfunction "2_2") (pintype "passive"))
      (node (ref "C22") (pin "2") (pinfunction "2_2") (pintype "passive"))
      (node (ref "C23") (pin "1") (pinfunction "1_1") (pintype "passive"))
      (node (ref "C24") (pin "1") (pinfunction "1_1") (pintype "passive"))
      (node (ref "C26") (pin "1") (pinfunction "1_1") (pintype "passive"))
      (node (ref "C27") (pin "1") (pinfunction "1_1") (pintype "passive"))
      (node (ref "C28") (pin "1") (pinfunction "1_1") (pintype "passive"))
      (node (ref "C29") (pin "1") (pinfunction "1_1") (pintype "passive"))
      (node (ref "C3") (pin "2") (pinfunction "2_2") (pintype "passive"))
      (node (ref "C30") (pin "2") (pinfunction "2_2") (pintype "passive"))
      (node (ref "C31") (pin "2") (pinfunction "2_2") (pintype "passive"))
      (node (ref "C32") (pin "2") (pinfunction "2_2") (pintype "passive"))
      (node (ref "C33") (pin "1") (pinfunction "1_1") (pintype "passive"))
      (node (ref "C34") (pin "2") (pinfunction "2_2") (pintype "passive"))
      (node (ref "C35") (pin "2") (pinfunction "2_2") (pintype "passive"))
      (node (ref "C36") (pin "2") (pinfunction "2_2") (pintype "passive"))
      (node (ref "C37") (pin "2") (pinfunction "2_2") (pintype "passive"))
      (node (ref "C38") (pin "2") (pinfunction "2_2") (pintype "passive"))
      (node (ref "C39") (pin "2") (pinfunction "2_2") (pintype "passive"))
      (node (ref "C4") (pin "2") (pinfunction "2_2") (pintype "passive"))
      (node (ref "C40") (pin "2") (pinfunction "2_2") (pintype "passive"))
      (node (ref "C41") (pin "2") (pinfunction "2_2") (pintype "passive"))
      (node (ref "C42") (pin "1") (pinfunction "1_1") (pintype "passive"))
      (node (ref "C43") (pin "2") (pinfunction "2_2") (pintype "passive"))
      (node (ref "C44") (pin "2") (pinfunction "2_2") (pintype "passive"))
      (node (ref "C45") (pin "2") (pinfunction "2_2") (pintype "passive"))
      (node (ref "C46") (pin "2") (pinfunction "2_2") (pintype "passive"))
      (node (ref "C5") (pin "2") (pinfunction "2_2") (pintype "passive"))
      (node (ref "C6") (pin "2") (pinfunction "2_2") (pintype "passive"))
      (node (ref "C7") (pin "2") (pinfunction "2_2") (pintype "passive"))
      (node (ref "C8") (pin "2") (pinfunction "2_2") (pintype "passive"))
      (node (ref "D11") (pin "2") (pinfunction "A_2") (pintype "passive"))
      (node (ref "D12") (pin "1") (pinfunction "C_1") (pintype "passive"))
      (node (ref "D5") (pin "2") (pinfunction "Case_2") (pintype "passive"))
      (node (ref "D6") (pin "2") (pinfunction "Case_2") (pintype "passive"))
      (node (ref "IC1") (pin "2") (pinfunction "GND_2") (pintype "power_in"))
      (node (ref "IC2") (pin "4") (pinfunction "GND_4") (pintype "power_in"))
      (node (ref "IC2") (pin "9") (pinfunction "EP_9") (pintype "power_in"))
      (node (ref "IC3") (pin "2") (pinfunction "GND_2") (pintype "power_in"))
      (node (ref "IC4") (pin "4") (pinfunction "GND_4") (pintype "power_in"))
      (node (ref "IC4") (pin "9") (pinfunction "EP_9") (pintype "power_in"))
      (node (ref "IC5") (pin "1") (pinfunction "GND_1") (pintype "power_in"))
      (node (ref "IC6") (pin "1") (pinfunction "GND_1") (pintype "power_in"))
      (node (ref "IC7") (pin "2") (pinfunction "GND_2") (pintype "power_in"))
      (node (ref "IC8") (pin "1") (pinfunction "GND_1") (pintype "power_in"))
      (node (ref "J1") (pin "2") (pinfunction "2_2") (pintype "bidirectional"))
      (node (ref "J3") (pin "2") (pinfunction "2_2") (pintype "bidirectional"))
      (node (ref "MSBOX1") (pin "1") (pinfunction "1_1") (pintype "passive"))
      (node (ref "MSBOX1") (pin "10") (pinfunction "10_10") (pintype "passive"))
      (node (ref "MSBOX1") (pin "11") (pinfunction "11_11") (pintype "passive"))
      (node (ref "MSBOX1") (pin "12") (pinfunction "12_12") (pintype "passive"))
      (node (ref "MSBOX1") (pin "13") (pinfunction "13_13") (pintype "passive"))
      (node (ref "MSBOX1") (pin "14") (pinfunction "14_14") (pintype "passive"))
      (node (ref "MSBOX1") (pin "15") (pinfunction "15_15") (pintype "passive"))
      (node (ref "MSBOX1") (pin "16") (pinfunction "16_16") (pintype "passive"))
      (node (ref "MSBOX1") (pin "17") (pinfunction "17_17") (pintype "passive"))
      (node (ref "MSBOX1") (pin "18") (pinfunction "18_18") (pintype "passive"))
      (node (ref "MSBOX1") (pin "19") (pinfunction "19_19") (pintype "passive"))
      (node (ref "MSBOX1") (pin "2") (pinfunction "2_2") (pintype "passive"))
      (node (ref "MSBOX1") (pin "20") (pinfunction "20_20") (pintype "passive"))
      (node (ref "MSBOX1") (pin "3") (pinfunction "3_3") (pintype "passive"))
      (node (ref "MSBOX1") (pin "4") (pinfunction "4_4") (pintype "passive"))
      (node (ref "MSBOX1") (pin "5") (pinfunction "5_5") (pintype "passive"))
      (node (ref "MSBOX1") (pin "6") (pinfunction "6_6") (pintype "passive"))
      (node (ref "MSBOX1") (pin "7") (pinfunction "7_7") (pintype "passive"))
      (node (ref "MSBOX1") (pin "8") (pinfunction "8_8") (pintype "passive"))
      (node (ref "MSBOX1") (pin "9") (pinfunction "9_9") (pintype "passive"))
      (node (ref "MSBOX2") (pin "1") (pinfunction "1_1") (pintype "passive"))
      (node (ref "MSBOX2") (pin "2") (pinfunction "2_2") (pintype "passive"))
      (node (ref "MSBOX2") (pin "3") (pinfunction "3_3") (pintype "passive"))
      (node (ref "MSBOX2") (pin "4") (pinfunction "4_4") (pintype "passive"))
      (node (ref "MSBOX2") (pin "5") (pinfunction "5_5") (pintype "passive"))
      (node (ref "MSBOX2") (pin "6") (pinfunction "6_6") (pintype "passive"))
      (node (ref "MSBOX2") (pin "7") (pinfunction "7_7") (pintype "passive"))
      (node (ref "MSBOX2") (pin "8") (pinfunction "8_8") (pintype "passive"))
      (node (ref "R10") (pin "1") (pinfunction "1_1") (pintype "passive"))
      (node (ref "R13") (pin "1") (pinfunction "1_1") (pintype "passive"))
      (node (ref "R16") (pin "2") (pinfunction "2_2") (pintype "passive"))
      (node (ref "R17") (pin "1") (pinfunction "1_1") (pintype "passive"))
      (node (ref "R2") (pin "1") (pinfunction "1_1") (pintype "passive"))
      (node (ref "R24") (pin "2") (pinfunction "2_2") (pintype "passive"))
      (node (ref "R25") (pin "2") (pinfunction "2_2") (pintype "passive"))
      (node (ref "R9") (pin "2") (pinfunction "2_2") (pintype "passive"))
      (node (ref "T3") (pin "3") (pinfunction "C_3") (pintype "passive"))
      (node (ref "T5") (pin "3") (pinfunction "C_3") (pintype "passive"))
    )
    (net (code "8") (name "N15V0") (class "Default")
      (node (ref "C17") (pin "2") (pinfunction "2_2") (pintype "passive"))
      (node (ref "C18") (pin "2") (pinfunction "2_2") (pintype "passive"))
      (node (ref "D10") (pin "1") (pinfunction "C_1") (pintype "passive"))
      (node (ref "D7") (pin "1") (pinfunction "C_1") (pintype "passive"))
      (node (ref "D8") (pin "1") (pinfunction "C_1") (pintype "passive"))
      (node (ref "D9") (pin "1") (pinfunction "C_1") (pintype "passive"))
      (node (ref "L4") (pin "1") (pinfunction "1_1") (pintype "passive"))
    )
    (net (code "9") (name "Net-(C19-Pad2)") (class "Default")
      (node (ref "C19") (pin "2") (pinfunction "2_2") (pintype "passive"))
      (node (ref "C20") (pin "1") (pinfunction "1_1") (pintype "passive"))
    )
    (net (code "10") (name "Net-(D1-C)") (class "Default")
      (node (ref "C3") (pin "1") (pinfunction "1_1") (pintype "passive"))
      (node (ref "C4") (pin "1") (pinfunction "1_1") (pintype "passive"))
      (node (ref "D1") (pin "1") (pinfunction "C_1") (pintype "passive"))
      (node (ref "IC1") (pin "3") (pinfunction "IN_3") (pintype "input"))
    )
    (net (code "11") (name "Net-(D2-C)") (class "Default")
      (node (ref "C7") (pin "1") (pinfunction "1_1") (pintype "passive"))
      (node (ref "C8") (pin "1") (pinfunction "1_1") (pintype "passive"))
      (node (ref "D2") (pin "1") (pinfunction "C_1") (pintype "passive"))
      (node (ref "IC2") (pin "5") (pinfunction "EN_5") (pintype "input"))
      (node (ref "IC2") (pin "8") (pinfunction "IN_8") (pintype "input"))
    )
    (net (code "12") (name "Net-(D3-C)") (class "Default")
      (node (ref "C12") (pin "1") (pinfunction "1_1") (pintype "passive"))
      (node (ref "C13") (pin "1") (pinfunction "1_1") (pintype "passive"))
      (node (ref "D3") (pin "1") (pinfunction "C_1") (pintype "passive"))
      (node (ref "IC3") (pin "3") (pinfunction "IN_3") (pintype "input"))
    )
    (net (code "13") (name "Net-(D4-C)") (class "Default")
      (node (ref "C37") (pin "1") (pinfunction "1_1") (pintype "passive"))
      (node (ref "C38") (pin "1") (pinfunction "1_1") (pintype "passive"))
      (node (ref "D4") (pin "1") (pinfunction "C_1") (pintype "passive"))
      (node (ref "IC7") (pin "3") (pinfunction "IN_3") (pintype "input"))
    )
    (net (code "14") (name "Net-(D5-Anode)") (class "Default")
      (node (ref "C19") (pin "1") (pinfunction "1_1") (pintype "passive"))
      (node (ref "D5") (pin "3") (pinfunction "Anode_3") (pintype "passive"))
      (node (ref "D6") (pin "1") (pinfunction "Cathode_1") (pintype "passive"))
      (node (ref "R3") (pin "1") (pinfunction "1_1") (pintype "passive"))
      (node (ref "U1") (pin "2") (pinfunction "IN-_2") (pintype "input"))
    )
    (net (code "15") (name "Net-(D5-Cathode)") (class "Default")
      (node (ref "C10") (pin "1") (pinfunction "1_1") (pintype "passive"))
      (node (ref "C11") (pin "1") (pinfunction "1_1") (pintype "passive"))
      (node (ref "C9") (pin "2") (pinfunction "2_2") (pintype "passive"))
      (node (ref "D5") (pin "1") (pinfunction "Cathode_1") (pintype "passive"))
      (node (ref "IC2") (pin "1") (pinfunction "OUT_1") (pintype "power_in"))
      (node (ref "R1") (pin "2") (pinfunction "2_2") (pintype "passive"))
    )
    (net (code "16") (name "Net-(D6-Anode)") (class "Default")
      (node (ref "C25") (pin "2") (pinfunction "2_2") (pintype "passive"))
      (node (ref "C26") (pin "2") (pinfunction "2_2") (pintype "passive"))
      (node (ref "C27") (pin "2") (pinfunction "2_2") (pintype "passive"))
      (node (ref "D6") (pin "3") (pinfunction "Anode_3") (pintype "passive"))
      (node (ref "IC4") (pin "1") (pinfunction "OUT_1") (pintype "power_in"))
      (node (ref "R12") (pin "2") (pinfunction "2_2") (pintype "passive"))
    )
    (net (code "17") (name "Net-(D7-A)") (class "Default")
      (node (ref "C29") (pin "2") (pinfunction "2_2") (pintype "passive"))
      (node (ref "C30") (pin "1") (pinfunction "1_1") (pintype "passive"))
      (node (ref "D7") (pin "2") (pinfunction "A_2") (pintype "passive"))
      (node (ref "IC5") (pin "2") (pinfunction "IN_2") (pintype "input"))
      (node (ref "IC5") (pin "4") (pinfunction "IN_4") (pintype "input"))
    )
    (net (code "18") (name "Net-(D8-A)") (class "Default")
      (node (ref "C33") (pin "2") (pinfunction "2_2") (pintype "passive"))
      (node (ref "C34") (pin "1") (pinfunction "1_1") (pintype "passive"))
      (node (ref "D8") (pin "2") (pinfunction "A_2") (pintype "passive"))
      (node (ref "IC6") (pin "2") (pinfunction "IN_2") (pintype "input"))
      (node (ref "IC6") (pin "4") (pinfunction "IN_4") (pintype "input"))
    )
    (net (code "19") (name "Net-(D9-A)") (class "Default")
      (node (ref "C23") (pin "2") (pinfunction "2_2") (pintype "passive"))
      (node (ref "C24") (pin "2") (pinfunction "2_2") (pintype "passive"))
      (node (ref "D9") (pin "2") (pinfunction "A_2") (pintype "passive"))
      (node (ref "IC4") (pin "5") (pinfunction "EN_5") (pintype "input"))
      (node (ref "IC4") (pin "8") (pinfunction "IN_8") (pintype "input"))
    )
    (net (code "20") (name "Net-(D10-A)") (class "Default")
      (node (ref "C42") (pin "2") (pinfunction "2_2") (pintype "passive"))
      (node (ref "C43") (pin "1") (pinfunction "1_1") (pintype "passive"))
      (node (ref "D10") (pin "2") (pinfunction "A_2") (pintype "passive"))
      (node (ref "IC8") (pin "2") (pinfunction "IN_2") (pintype "input"))
      (node (ref "IC8") (pin "4") (pinfunction "IN_4") (pintype "input"))
    )
    (net (code "21") (name "Net-(D11-C)") (class "Default")
      (node (ref "D11") (pin "1") (pinfunction "C_1") (pintype "passive"))
      (node (ref "J1") (pin "3") (pinfunction "3_3") (pintype "bidirectional"))
      (node (ref "L1") (pin "2") (pinfunction "2_2") (pintype "passive"))
    )
    (net (code "22") (name "Net-(D12-A)") (class "Default")
      (node (ref "D12") (pin "2") (pinfunction "A_2") (pintype "passive"))
      (node (ref "J1") (pin "1") (pinfunction "1_1") (pintype "bidirectional"))
      (node (ref "L3") (pin "2") (pinfunction "2_2") (pintype "passive"))
    )
    (net (code "23") (name "Net-(IC2-FB)") (class "Default")
      (node (ref "C9") (pin "1") (pinfunction "1_1") (pintype "passive"))
      (node (ref "IC2") (pin "2") (pinfunction "FB_2") (pintype "passive"))
      (node (ref "R1") (pin "1") (pinfunction "1_1") (pintype "passive"))
      (node (ref "R2") (pin "2") (pinfunction "2_2") (pintype "passive"))
    )
    (net (code "24") (name "Net-(IC2-NR{slash}SS)") (class "Default")
      (node (ref "C16") (pin "2") (pinfunction "2_2") (pintype "passive"))
      (node (ref "IC2") (pin "6") (pinfunction "NR/SS_6") (pintype "output"))
    )
    (net (code "25") (name "Net-(IC4-FB)") (class "Default")
      (node (ref "C25") (pin "1") (pinfunction "1_1") (pintype "passive"))
      (node (ref "IC4") (pin "2") (pinfunction "FB_2") (pintype "passive"))
      (node (ref "P2") (pin "1") (pinfunction "CCW_1") (pintype "passive"))
      (node (ref "P2") (pin "2") (pinfunction "W_2") (pintype "passive"))
      (node (ref "R13") (pin "2") (pinfunction "2_2") (pintype "passive"))
    )
    (net (code "26") (name "Net-(IC4-NR{slash}SS)") (class "Default")
      (node (ref "C28") (pin "2") (pinfunction "2_2") (pintype "passive"))
      (node (ref "IC4") (pin "6") (pinfunction "NR/SS_6") (pintype "output"))
    )
    (net (code "27") (name "Net-(J3-Pad1)") (class "Default")
      (node (ref "J3") (pin "1") (pinfunction "1_1") (pintype "bidirectional"))
      (node (ref "R6") (pin "1") (pinfunction "1_1") (pintype "passive"))
    )
    (net (code "28") (name "Net-(L1-Pad1)") (class "Default")
      (node (ref "L1") (pin "1") (pinfunction "1_1") (pintype "passive"))
      (node (ref "L2") (pin "2") (pinfunction "2_2") (pintype "passive"))
    )
    (net (code "29") (name "Net-(L3-Pad1)") (class "Default")
      (node (ref "L3") (pin "1") (pinfunction "1_1") (pintype "passive"))
      (node (ref "L4") (pin "2") (pinfunction "2_2") (pintype "passive"))
    )
    (net (code "30") (name "Net-(LD1A-A)") (class "Default")
      (node (ref "LD1") (pin "2") (pinfunction "A_2") (pintype "passive"))
      (node (ref "R19") (pin "2") (pinfunction "2_2") (pintype "passive"))
    )
    (net (code "31") (name "Net-(LD1A-C)") (class "Default")
      (node (ref "LD1") (pin "1") (pinfunction "C_1") (pintype "passive"))
      (node (ref "R18") (pin "2") (pinfunction "2_2") (pintype "passive"))
      (node (ref "T3") (pin "2") (pinfunction "E_2") (pintype "passive"))
    )
    (net (code "32") (name "Net-(LD1B-A)") (class "Default")
      (node (ref "LD1") (pin "4") (pinfunction "A_4") (pintype "passive"))
      (node (ref "R22") (pin "2") (pinfunction "2_2") (pintype "passive"))
    )
    (net (code "33") (name "Net-(LD1B-C)") (class "Default")
      (node (ref "LD1") (pin "3") (pinfunction "C_3") (pintype "passive"))
      (node (ref "R21") (pin "2") (pinfunction "2_2") (pintype "passive"))
      (node (ref "T5") (pin "2") (pinfunction "E_2") (pintype "passive"))
    )
    (net (code "34") (name "Net-(P1-CCW)") (class "Default")
      (node (ref "P1") (pin "1") (pinfunction "CCW_1") (pintype "passive"))
      (node (ref "R10") (pin "2") (pinfunction "2_2") (pintype "passive"))
      (node (ref "R5") (pin "2") (pinfunction "2_2") (pintype "passive"))
    )
    (net (code "35") (name "Net-(P1-CW)") (class "Default")
      (node (ref "P1") (pin "3") (pinfunction "CW_3") (pintype "passive"))
      (node (ref "R11") (pin "2") (pinfunction "2_2") (pintype "passive"))
      (node (ref "R17") (pin "2") (pinfunction "2_2") (pintype "passive"))
    )
    (net (code "36") (name "Net-(P1-W)") (class "Default")
      (node (ref "C21") (pin "1") (pinfunction "1_1") (pintype "passive"))
      (node (ref "P1") (pin "2") (pinfunction "W_2") (pintype "passive"))
      (node (ref "U1") (pin "3") (pinfunction "IN+_3") (pintype "input"))
    )
    (net (code "37") (name "Net-(P2-CW)") (class "Default")
      (node (ref "P2") (pin "3") (pinfunction "CW_3") (pintype "passive"))
      (node (ref "R12") (pin "1") (pinfunction "1_1") (pintype "passive"))
    )
    (net (code "38") (name "Net-(SW1-C)") (class "Default")
      (node (ref "R18") (pin "1") (pinfunction "1_1") (pintype "passive"))
      (node (ref "R19") (pin "1") (pinfunction "1_1") (pintype "passive"))
      (node (ref "R21") (pin "1") (pinfunction "1_1") (pintype "passive"))
      (node (ref "R22") (pin "1") (pinfunction "1_1") (pintype "passive"))
      (node (ref "SW1") (pin "2") (pinfunction "C_2") (pintype "bidirectional"))
    )
    (net (code "39") (name "Net-(T2-B)") (class "Default")
      (node (ref "C46") (pin "1") (pinfunction "1_1") (pintype "passive"))
      (node (ref "R23") (pin "1") (pinfunction "1_1") (pintype "passive"))
      (node (ref "T2") (pin "1") (pinfunction "B_1") (pintype "passive"))
      (node (ref "T4") (pin "2") (pinfunction "E_2") (pintype "passive"))
    )
    (net (code "40") (name "Net-(T2-C)") (class "Default")
      (node (ref "T2") (pin "3") (pinfunction "C_3") (pintype "passive"))
      (node (ref "T3") (pin "1") (pinfunction "B_1") (pintype "passive"))
    )
    (net (code "41") (name "Net-(T2-E)") (class "Default")
      (node (ref "R20") (pin "2") (pinfunction "2_2") (pintype "passive"))
      (node (ref "R24") (pin "1") (pinfunction "1_1") (pintype "passive"))
      (node (ref "T2") (pin "2") (pinfunction "E_2") (pintype "passive"))
    )
    (net (code "42") (name "Net-(T4-B)") (class "Default")
      (node (ref "R25") (pin "1") (pinfunction "1_1") (pintype "passive"))
      (node (ref "R26") (pin "2") (pinfunction "2_2") (pintype "passive"))
      (node (ref "T4") (pin "1") (pinfunction "B_1") (pintype "passive"))
    )
    (net (code "43") (name "Net-(T4-C)") (class "Default")
      (node (ref "T4") (pin "3") (pinfunction "C_3") (pintype "passive"))
      (node (ref "T5") (pin "1") (pinfunction "B_1") (pintype "passive"))
    )
    (net (code "44") (name "Net-(U1-OUT)") (class "Default")
      (node (ref "C20") (pin "2") (pinfunction "2_2") (pintype "passive"))
      (node (ref "R3") (pin "2") (pinfunction "2_2") (pintype "passive"))
      (node (ref "R7") (pin "2") (pinfunction "2_2") (pintype "passive"))
      (node (ref "U1") (pin "6") (pinfunction "OUT_6") (pintype "output"))
    )
    (net (code "45") (name "Net-(U2-IN+)") (class "Default")
      (node (ref "C22") (pin "1") (pinfunction "1_1") (pintype "passive"))
      (node (ref "R9") (pin "1") (pinfunction "1_1") (pintype "passive"))
      (node (ref "U2") (pin "3") (pinfunction "IN+_3") (pintype "input"))
    )
    (net (code "46") (name "Net-(U2-IN-)") (class "Default")
      (node (ref "R4") (pin "1") (pinfunction "1_1") (pintype "passive"))
      (node (ref "R7") (pin "1") (pinfunction "1_1") (pintype "passive"))
      (node (ref "U2") (pin "2") (pinfunction "IN-_2") (pintype "input"))
    )
    (net (code "47") (name "Net-(U2-OUT)") (class "Default")
      (node (ref "R15") (pin "2") (pinfunction "2_2") (pintype "passive"))
      (node (ref "R4") (pin "2") (pinfunction "2_2") (pintype "passive"))
      (node (ref "U2") (pin "6") (pinfunction "OUT_6") (pintype "output"))
    )
    (net (code "48") (name "Net-(U3-IN+)") (class "Default")
      (node (ref "C41") (pin "1") (pinfunction "1_1") (pintype "passive"))
      (node (ref "R16") (pin "1") (pinfunction "1_1") (pintype "passive"))
      (node (ref "U3") (pin "3") (pinfunction "IN+_3") (pintype "input"))
    )
    (net (code "49") (name "Net-(U3-IN-)") (class "Default")
      (node (ref "R14") (pin "1") (pinfunction "1_1") (pintype "passive"))
      (node (ref "R15") (pin "1") (pinfunction "1_1") (pintype "passive"))
      (node (ref "U3") (pin "2") (pinfunction "IN-_2") (pintype "input"))
    )
    (net (code "50") (name "Net-(U3-OUT)") (class "Default")
      (node (ref "R14") (pin "2") (pinfunction "2_2") (pintype "passive"))
      (node (ref "R23") (pin "2") (pinfunction "2_2") (pintype "passive"))
      (node (ref "R6") (pin "2") (pinfunction "2_2") (pintype "passive"))
      (node (ref "U3") (pin "6") (pinfunction "OUT_6") (pintype "output"))
    )
    (net (code "51") (name "P15V0") (class "Default")
      (node (ref "C1") (pin "1") (pinfunction "1_1") (pintype "passive"))
      (node (ref "C2") (pin "1") (pinfunction "1_1") (pintype "passive"))
      (node (ref "D1") (pin "2") (pinfunction "A_2") (pintype "passive"))
      (node (ref "D2") (pin "2") (pinfunction "A_2") (pintype "passive"))
      (node (ref "D3") (pin "2") (pinfunction "A_2") (pintype "passive"))
      (node (ref "D4") (pin "2") (pinfunction "A_2") (pintype "passive"))
      (node (ref "L2") (pin "1") (pinfunction "1_1") (pintype "passive"))
      (node (ref "SW1") (pin "1") (pinfunction "NO_1") (pintype "bidirectional"))
    )
    (net (code "52") (name "unconnected-(IC2-NC-Pad3)") (class "Default")
      (node (ref "IC2") (pin "3") (pinfunction "NC_3") (pintype "passive"))
    )
    (net (code "53") (name "unconnected-(IC4-NC-Pad3)") (class "Default")
      (node (ref "IC4") (pin "3") (pinfunction "NC_3") (pintype "passive"))
    )
    (net (code "54") (name "unconnected-(SW1-NC-Pad3)") (class "Default")
      (node (ref "SW1") (pin "3") (pinfunction "NC_3") (pintype "bidirectional"))
    )
    (net (code "55") (name "unconnected-(U1-NC-Pad1)") (class "Default")
      (node (ref "U1") (pin "1") (pinfunction "NC_1") (pintype "passive+no_connect"))
    )
    (net (code "56") (name "unconnected-(U1-NC-Pad5)") (class "Default")
      (node (ref "U1") (pin "5") (pinfunction "NC_5") (pintype "passive+no_connect"))
    )
    (net (code "57") (name "unconnected-(U1-~{DIS}-Pad8)") (class "Default")
      (node (ref "U1") (pin "8") (pinfunction "~{DIS}_8") (pintype "input+no_connect"))
    )
    (net (code "58") (name "unconnected-(U2-NC-Pad1)") (class "Default")
      (node (ref "U2") (pin "1") (pinfunction "NC_1") (pintype "passive+no_connect"))
    )
    (net (code "59") (name "unconnected-(U2-NC-Pad5)") (class "Default")
      (node (ref "U2") (pin "5") (pinfunction "NC_5") (pintype "passive+no_connect"))
    )
    (net (code "60") (name "unconnected-(U2-~{DIS}-Pad8)") (class "Default")
      (node (ref "U2") (pin "8") (pinfunction "~{DIS}_8") (pintype "input+no_connect"))
    )
    (net (code "61") (name "unconnected-(U3-NC-Pad1)") (class "Default")
      (node (ref "U3") (pin "1") (pinfunction "NC_1") (pintype "passive+no_connect"))
    )
    (net (code "62") (name "unconnected-(U3-NC-Pad5)") (class "Default")
      (node (ref "U3") (pin "5") (pinfunction "NC_5") (pintype "passive+no_connect"))
    )
    (net (code "63") (name "unconnected-(U3-~{DIS}-Pad8)") (class "Default")
      (node (ref "U3") (pin "8") (pinfunction "~{DIS}_8") (pintype "input+no_connect"))
    )
  )
)
